# Mram.net
KiCad netlist of a schematic drawn in Altium Designer
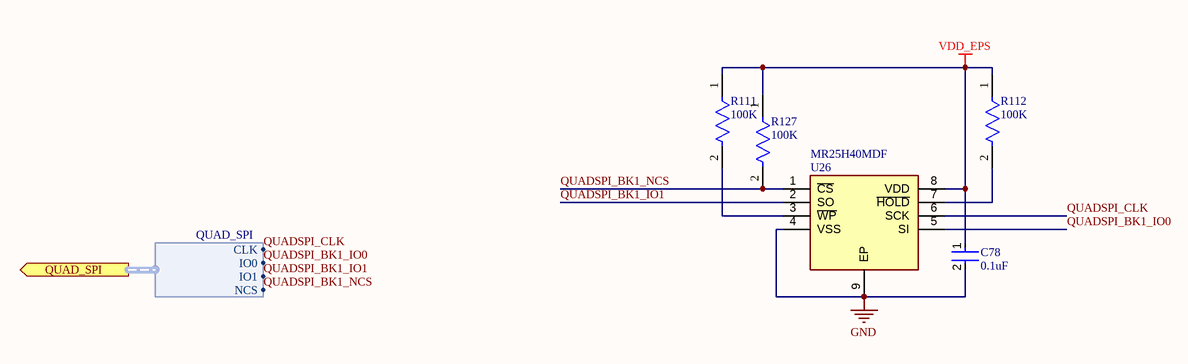
[diagram p0: Mram.SchDoc]

(export (version "E")
  (design (tool "Eeschema 10.0.6"))
  (components
    (comp (ref "C78")
      (value "0.1uF")
      (footprint "FP-C0603C-CF-MFG")
      (description "CAP CER 0.1UF 50V X7R 0603")
      (fields (field (name "TOLERANCE") "0.1") (field (name "MANUFACTURER") "KEMET"))
      (libsource (lib "Altium Content Vault") (part "b4654b650e69147ec39a6b967a45e02"))
    )
    (comp (ref "R111")
      (value "100K")
      (footprint "FP-ERA3A-MFG")
      (fields (field (name "TOLERANCE") "0.1%"))
      (libsource (lib "Altium Content Vault") (part "1029c3af85768c4190bb7ad29bc67b5"))
    )
    (comp (ref "R112")
      (value "100K")
      (footprint "FP-ERA3A-MFG")
      (fields (field (name "TOLERANCE") "0.1%"))
      (libsource (lib "Altium Content Vault") (part "1029c3af85768c4190bb7ad29bc67b5"))
    )
    (comp (ref "R127")
      (value "100K")
      (footprint "FP-ERA3A-MFG")
      (fields (field (name "TOLERANCE") "0.1%"))
      (libsource (lib "Altium Content Vault") (part "1029c3af85768c4190bb7ad29bc67b5"))
    )
    (comp (ref "U26")
      (value "MR25H40MDF")
      (footprint "SamacSys:SON127P600X500X90-9N-D")
      (description "Integrated Circuit")
      (fields (field (name "MOUSER PART NUMBER") "936-MR25H40MDF"))
      (libsource (lib "*") (part "MR25H40MDF"))
    )
  )
  (nets
    (net (code "2") (name "/QUADSPI_BK1_IO0") (class "Default")
      (node (ref "U26") (pin "5") (pinfunction "SI_5") (pintype "passive"))
    )
    (net (code "3") (name "/QUADSPI_BK1_IO1") (class "Default")
      (node (ref "U26") (pin "2") (pinfunction "SO_2") (pintype "passive"))
    )
    (net (code "4") (name "/QUADSPI_BK1_NCS") (class "Default")
      (node (ref "R127") (pin "2") (pinfunction "2_2") (pintype "passive"))
      (node (ref "U26") (pin "1") (pinfunction "~{CS}_1") (pintype "passive"))
    )
    (net (code "5") (name "/QUADSPI_CLK") (class "Default")
      (node (ref "U26") (pin "6") (pinfunction "SCK_6") (pintype "passive"))
    )
    (net (code "7") (name "GND") (class "Default")
      (node (ref "C78") (pin "2") (pinfunction "2_2") (pintype "passive"))
      (node (ref "U26") (pin "4") (pinfunction "VSS_4") (pintype "passive"))
      (node (ref "U26") (pin "9") (pinfunction "EP_9") (pintype "passive"))
    )
    (net (code "8") (name "Net-(U26-~{HOLD})") (class "Default")
      (node (ref "R112") (pin "2") (pinfunction "2_2") (pintype "passive"))
      (node (ref "U26") (pin "7") (pinfunction "~{HOLD}_7") (pintype "passive"))
    )
    (net (code "9") (name "Net-(U26-~{WP})") (class "Default")
      (node (ref "R111") (pin "2") (pinfunction "2_2") (pintype "passive"))
      (node (ref "U26") (pin "3") (pinfunction "~{WP}_3") (pintype "passive"))
    )
    (net (code "10") (name "VDD_EPS") (class "Default")
      (node (ref "C78") (pin "1") (pinfunction "1_1") (pintype "passive"))
      (node (ref "R111") (pin "1") (pinfunction "1_1") (pintype "passive"))
      (node (ref "R112") (pin "1") (pinfunction "1_1") (pintype "passive"))
      (node (ref "R127") (pin "1") (pinfunction "1_1") (pintype "passive"))
      (node (ref "U26") (pin "8") (pinfunction "VDD_8") (pintype "passive"))
    )
  )
)
